# uStar.net
KiCad netlist of a schematic drawn in EAGLE
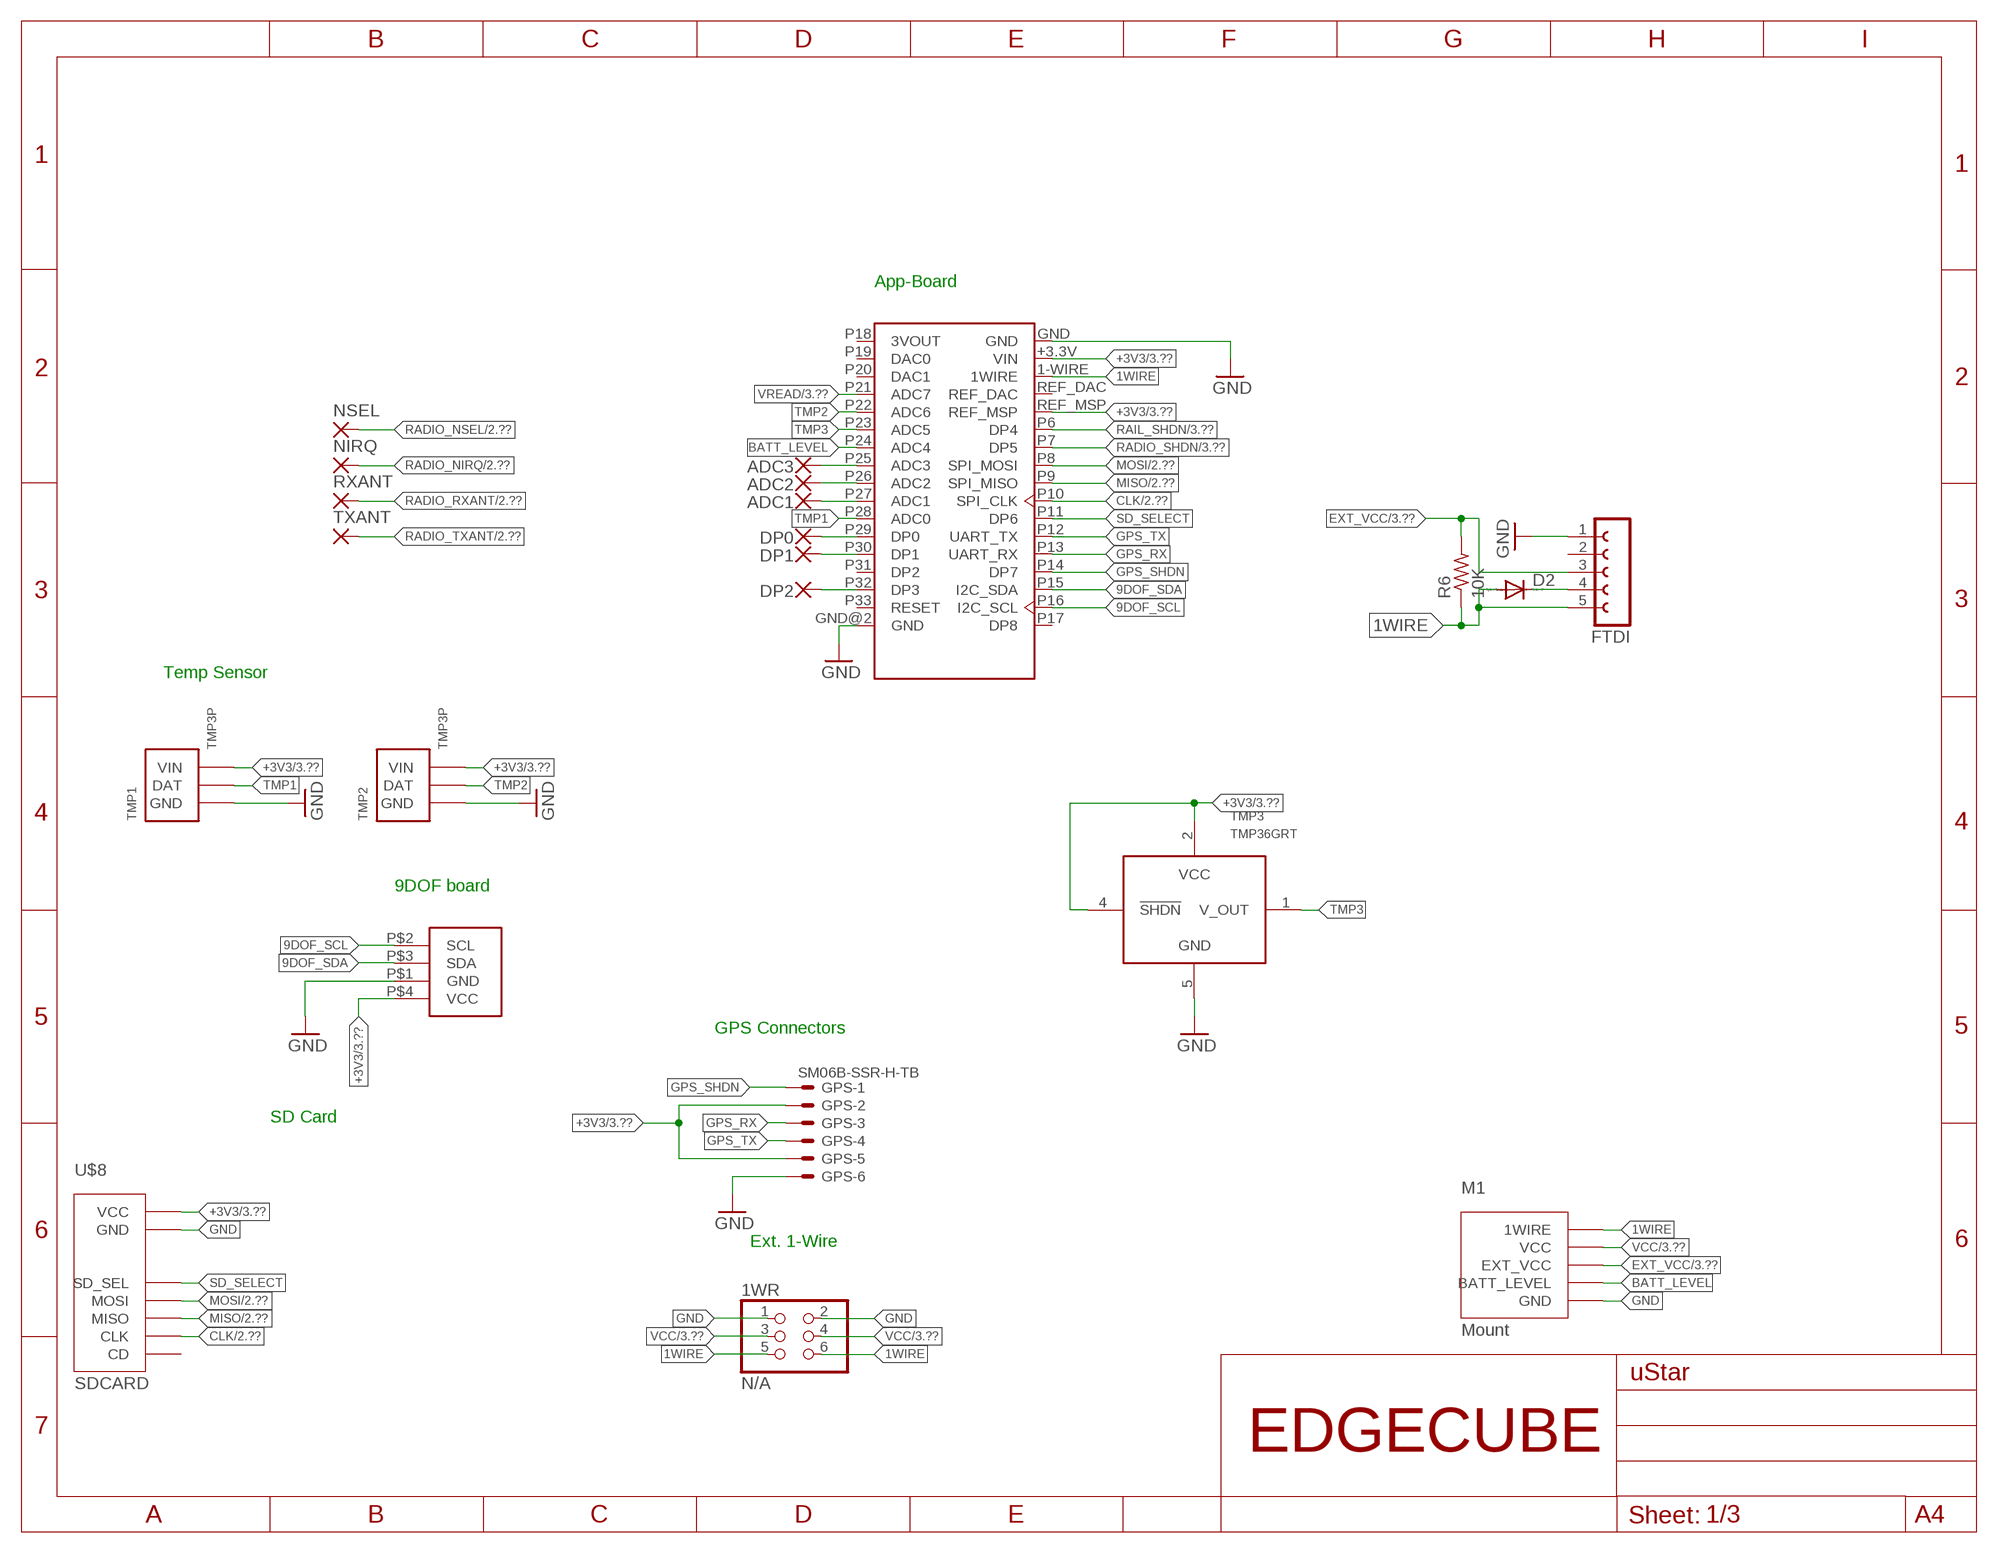
[diagram p0: schematic, sheet 1]
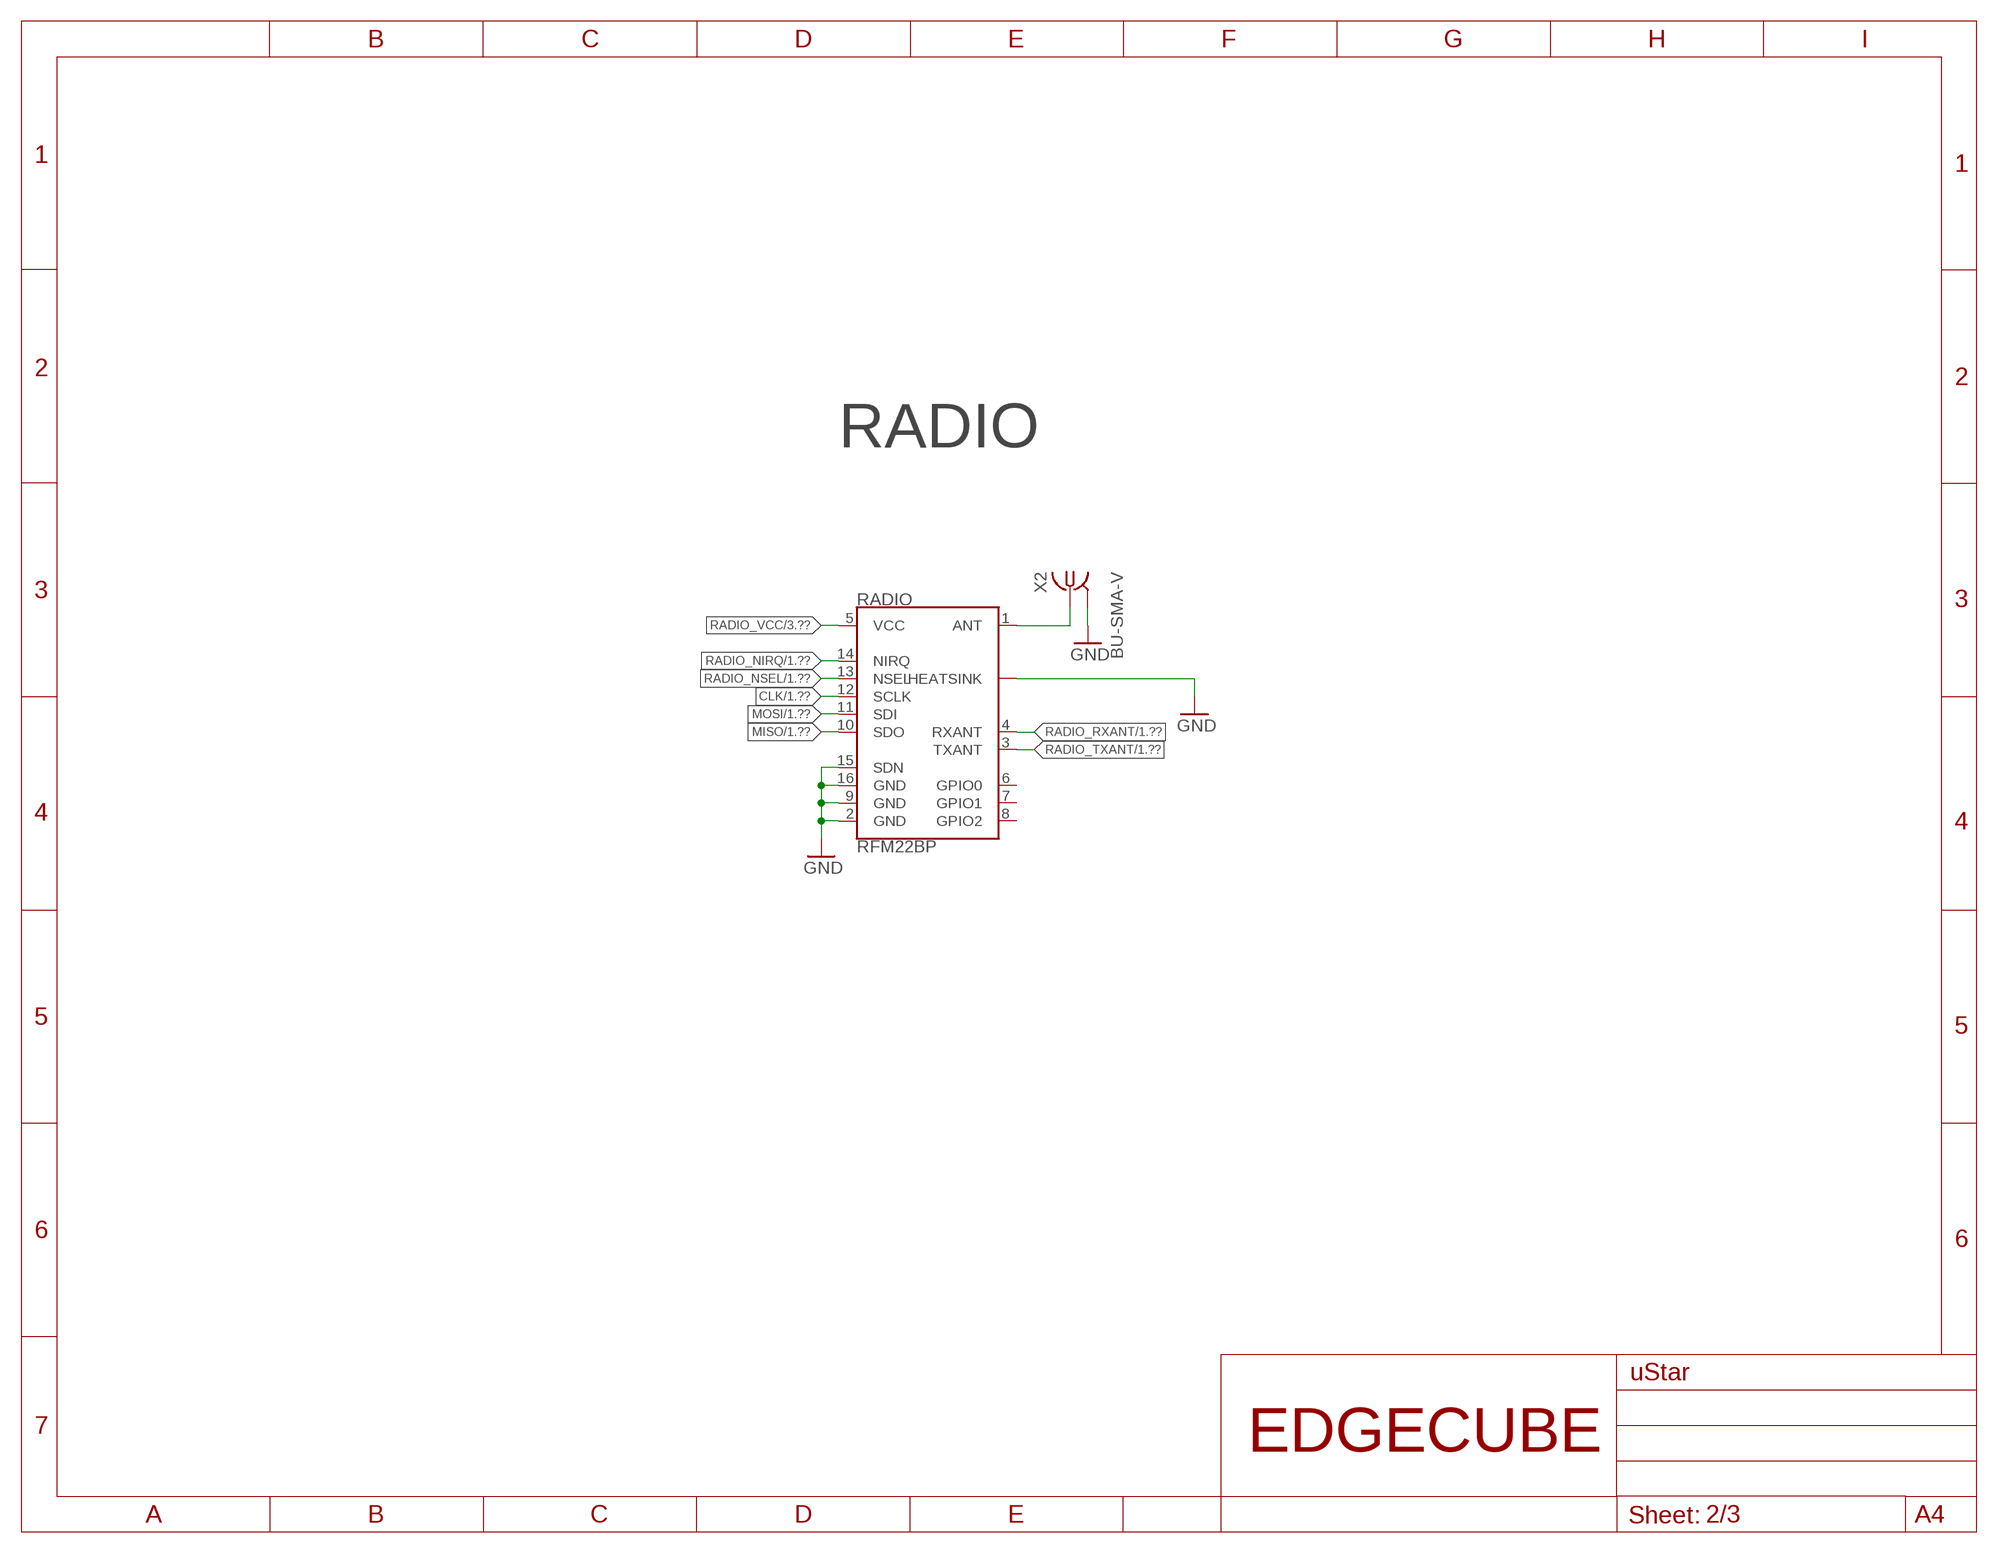
[diagram p1: schematic, sheet 2]
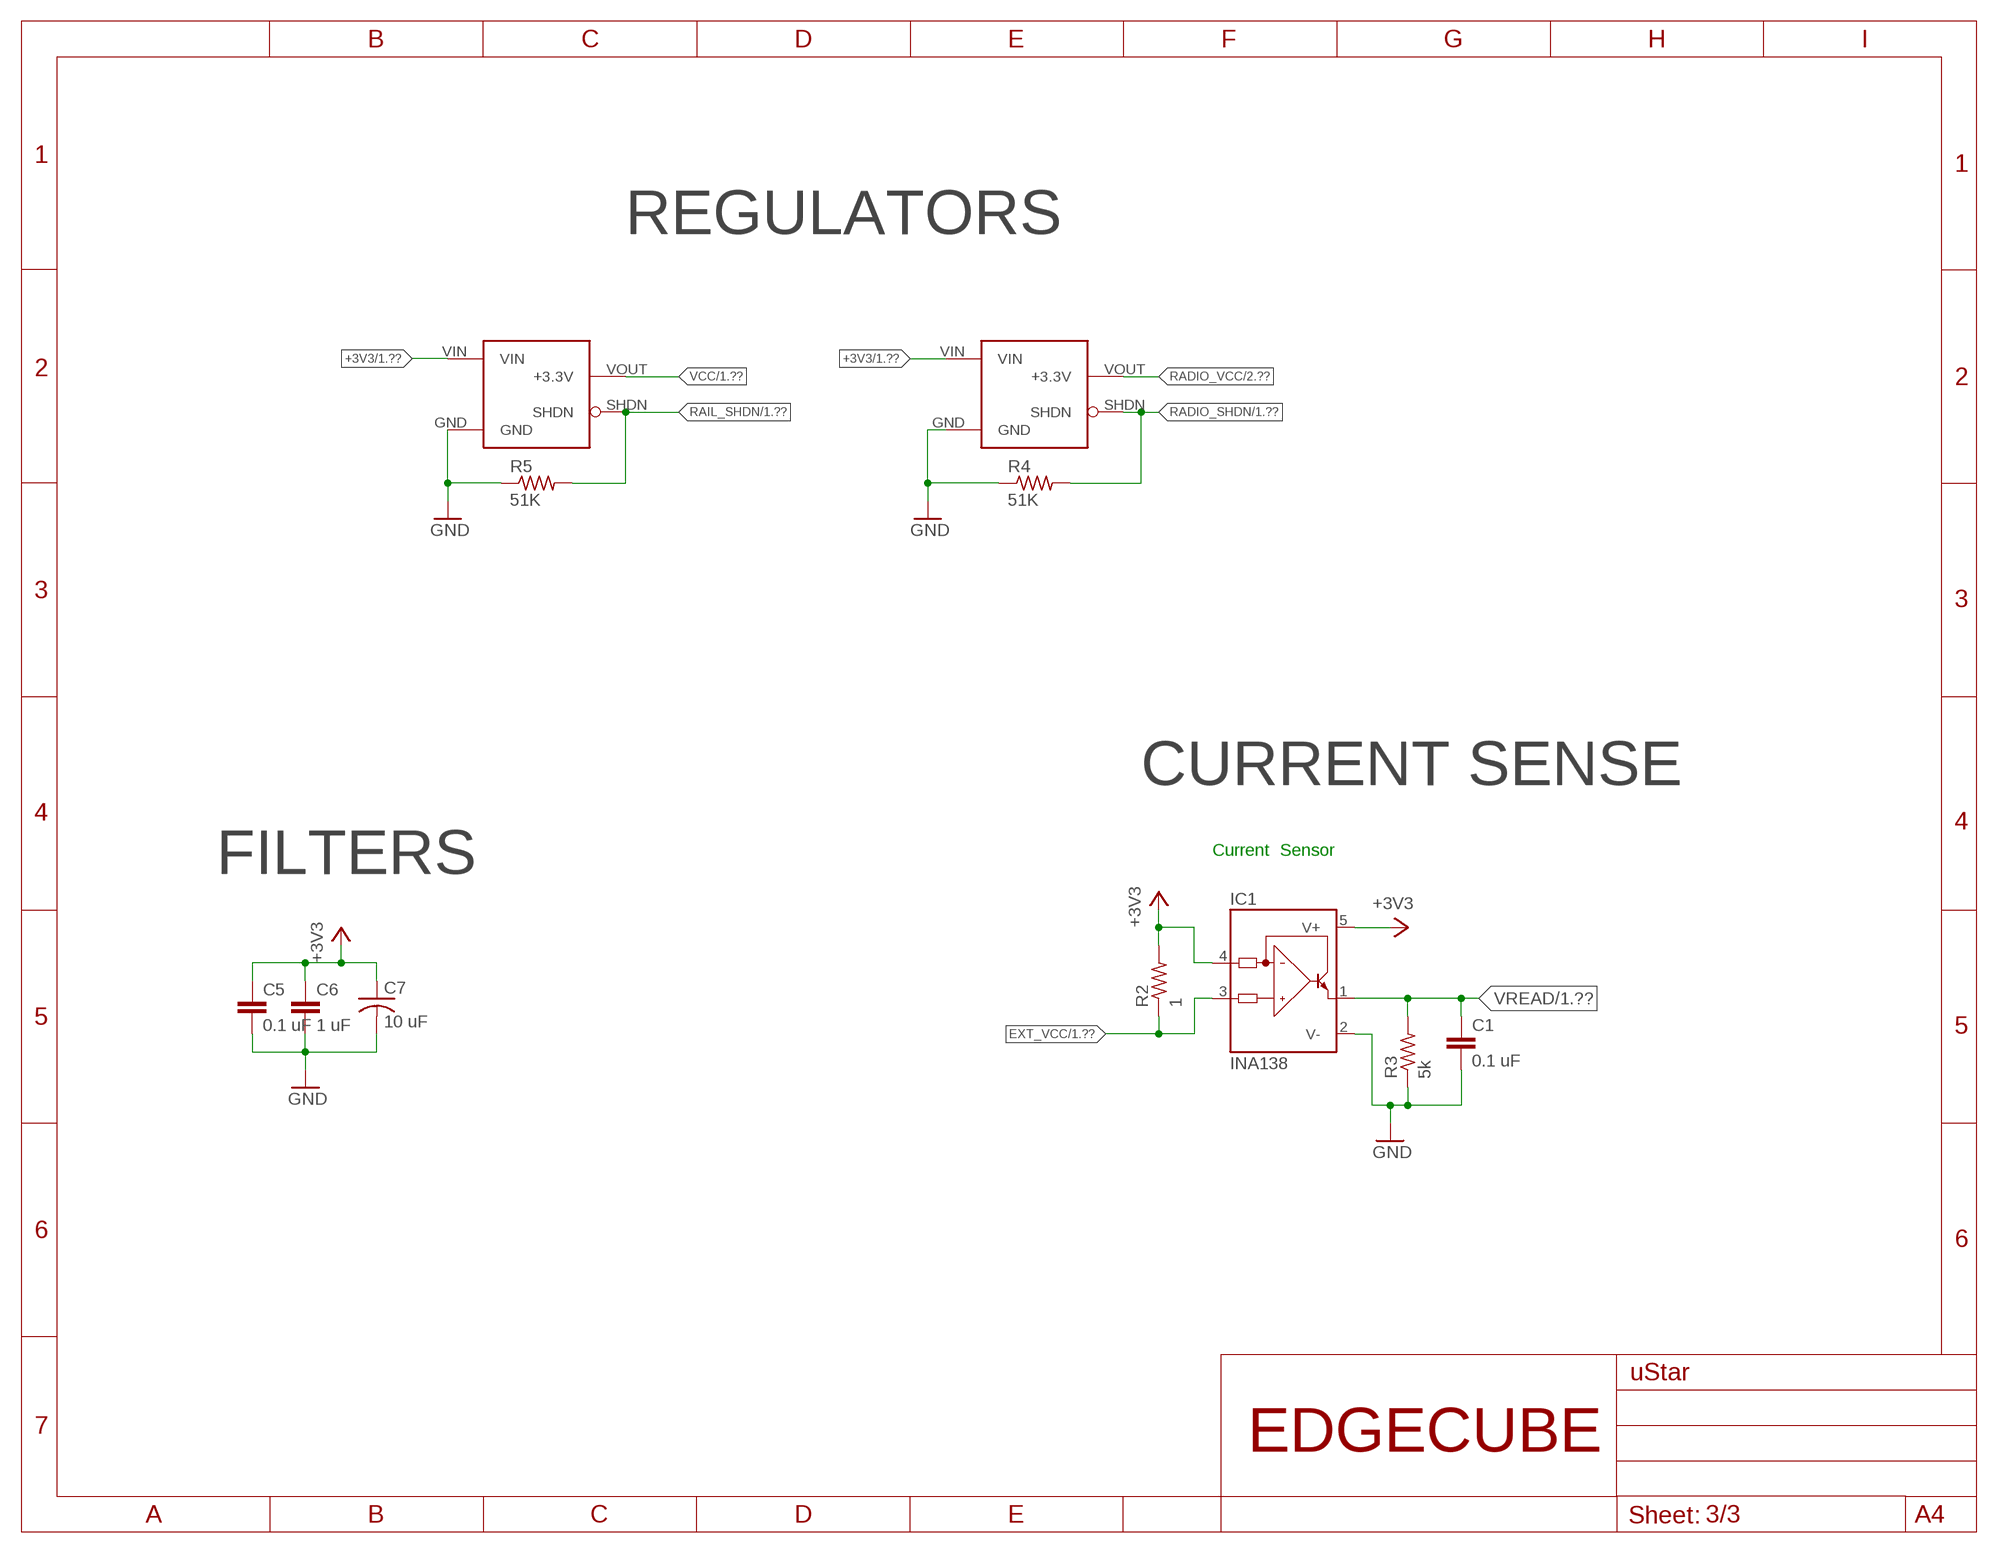
[diagram p2: schematic, sheet 3]

(export (version "E")
  (design (tool "Eeschema 10.0.6"))
  (components
    (comp (ref "C1")
      (value "0.1 uF")
      (footprint "eagle-import:C0603")
      (fields (field (name "MANUFACTURER") "AVX Corperation") (field (name "VOLTAGE") "50 V"))
      (libsource (lib "eagle-import") (part "CAP-0603-0.1UF"))
    )
    (comp (ref "C5")
      (value "0.1 uF")
      (footprint "eagle-import:C0603")
      (fields (field (name "MANUFACTURER") "AVX Corperation") (field (name "VOLTAGE") "50 V"))
      (libsource (lib "eagle-import") (part "CAP-0603-0.1UF"))
    )
    (comp (ref "C6")
      (value "1 uF")
      (footprint "eagle-import:C0603")
      (fields (field (name "MANUFACTURER") "Taiyo Yuden") (field (name "VOLTAGE") "25 V"))
      (libsource (lib "eagle-import") (part "CAP-0603-1UF"))
    )
    (comp (ref "C7")
      (value "10 uF")
      (footprint "eagle-import:C0805_POL")
      (fields (field (name "VOLTAGE") "10 V"))
      (libsource (lib "eagle-import") (part "CAP-0805-10UF-TANT"))
    )
    (comp (ref "IC1")
      (value "INA138")
      (footprint "eagle-import:SOT23-5")
      (fields (field (name "MF") "TEXAS INSTRUMENTS") (field (name "MPN") "INA138NA/250"))
      (libsource (lib "eagle-import") (part "INA138"))
    )
    (comp (ref "R2")
      (value "1")
      (footprint "eagle-import:R0603")
      (libsource (lib "eagle-import") (part "R-US_R0603"))
    )
    (comp (ref "R3")
      (value "5k")
      (footprint "eagle-import:R0603")
      (libsource (lib "eagle-import") (part "R-US_R0603"))
    )
    (comp (ref "R4")
      (value "51K")
      (footprint "eagle-import:R0603")
      (fields (field (name "MANUFACTURER") "Vishay Dale") (field (name "POWER") "0.1W"))
      (libsource (lib "eagle-import") (part "RES-0603-51K"))
    )
    (comp (ref "R5")
      (value "51K")
      (footprint "eagle-import:R0603")
      (fields (field (name "MANUFACTURER") "Vishay Dale") (field (name "POWER") "0.1W"))
      (libsource (lib "eagle-import") (part "RES-0603-51K"))
    )
    (comp (ref "U$3")
      (value "S7V8F3_VOLT_REG-3V3_1AHORZ-DOWN")
      (footprint "eagle-import:S7V_DOWN")
      (libsource (lib "eagle-import") (part "S7V8F3_VOLT_REG-3V3_1AHORZ-DOWN"))
    )
    (comp (ref "U$7")
      (value "S7V8F3_VOLT_REG-3V3_1AHORZ-DOWN")
      (footprint "eagle-import:S7V_DOWN")
      (libsource (lib "eagle-import") (part "S7V8F3_VOLT_REG-3V3_1AHORZ-DOWN"))
    )
    (comp (ref "1WR")
      (value "N/A")
      (footprint "eagle-import:2X03")
      (libsource (lib "eagle-import") (part "PINHD-2X3"))
    )
    (comp (ref "ADC1")
      (value "1,6/0,9")
      (footprint "eagle-import:1,6_0,9")
      (libsource (lib "eagle-import") (part "1,6/0,9"))
    )
    (comp (ref "ADC2")
      (value "1,6/0,9")
      (footprint "eagle-import:1,6_0,9")
      (libsource (lib "eagle-import") (part "1,6/0,9"))
    )
    (comp (ref "ADC3")
      (value "1,6/0,9")
      (footprint "eagle-import:1,6_0,9")
      (libsource (lib "eagle-import") (part "1,6/0,9"))
    )
    (comp (ref "D2")
      (value "D-B260A")
      (footprint "eagle-import:SMA-DO214AC")
      (fields (field (name "MANUFACTURER") "Diodes Incorporated") (field (name "VOLTAGE") "60V"))
      (libsource (lib "eagle-import") (part "D-B260A"))
    )
    (comp (ref "DP0")
      (value "1,6/0,9")
      (footprint "eagle-import:1,6_0,9")
      (libsource (lib "eagle-import") (part "1,6/0,9"))
    )
    (comp (ref "DP1")
      (value "1,6/0,9")
      (footprint "eagle-import:1,6_0,9")
      (libsource (lib "eagle-import") (part "1,6/0,9"))
    )
    (comp (ref "DP2")
      (value "1,6/0,9")
      (footprint "eagle-import:1,6_0,9")
      (libsource (lib "eagle-import") (part "1,6/0,9"))
    )
    (comp (ref "FTDI")
      (value "FE05-1")
      (footprint "eagle-import:FE05-1")
      (libsource (lib "eagle-import") (part "FE05-1"))
    )
    (comp (ref "GPS")
      (value "SM06B-SSR-H-TB")
      (footprint "eagle-import:SM06B-SSR-H-TB")
      (libsource (lib "eagle-import") (part "SM06B-SSR-H-TB"))
    )
    (comp (ref "M1")
      (value "Mount")
      (footprint "eagle-import:4X8MOUNT")
      (libsource (lib "eagle-import") (part "4X8MOUNT"))
    )
    (comp (ref "NIRQ")
      (value "1,6/0,9")
      (footprint "eagle-import:1,6_0,9")
      (libsource (lib "eagle-import") (part "1,6/0,9"))
    )
    (comp (ref "NSEL")
      (value "1,6/0,9")
      (footprint "eagle-import:1,6_0,9")
      (libsource (lib "eagle-import") (part "1,6/0,9"))
    )
    (comp (ref "R6")
      (value "10K")
      (footprint "eagle-import:R0603")
      (fields (field (name "MANUFACTURER") "Vishay Dale") (field (name "POWER") "0.1W"))
      (libsource (lib "eagle-import") (part "RES-0603-10K"))
    )
    (comp (ref "RXANT")
      (value "1,6/0,9")
      (footprint "eagle-import:1,6_0,9")
      (libsource (lib "eagle-import") (part "1,6/0,9"))
    )
    (comp (ref "TMP1")
      (value "TMP3P")
      (footprint "eagle-import:TMP3P")
      (libsource (lib "eagle-import") (part "TMP3P"))
    )
    (comp (ref "TMP2")
      (value "TMP3P")
      (footprint "eagle-import:TMP3P")
      (libsource (lib "eagle-import") (part "TMP3P"))
    )
    (comp (ref "TMP3")
      (value "TMP36GRT")
      (footprint "eagle-import:SOT-23-5")
      (fields (field (name "MANUFACTURER") "Analog Devices Inc.") (field (name "VOLTAGE") "2.7V-5.5V"))
      (libsource (lib "eagle-import") (part "TMP36GRT"))
    )
    (comp (ref "TXANT")
      (value "1,6/0,9")
      (footprint "eagle-import:1,6_0,9")
      (libsource (lib "eagle-import") (part "1,6/0,9"))
    )
    (comp (ref "U$1")
      (value "App-Board 1.2/1.3")
      (footprint "eagle-import:APPCORE_RECEIVER")
      (libsource (lib "eagle-import") (part "APP_CORE"))
    )
    (comp (ref "U$5")
      (value "9DOF")
      (footprint "eagle-import:9DOF")
      (libsource (lib "eagle-import") (part "9DOF"))
    )
    (comp (ref "U$8")
      (value "SDCARD")
      (footprint "eagle-import:SDCARD")
      (libsource (lib "eagle-import") (part "SDCARD"))
    )
    (comp (ref "RADIO")
      (value "RFM22BP")
      (footprint "eagle-import:RFM22BP")
      (fields (field (name "MANUFACTURER") "HOPERF Electronic"))
      (libsource (lib "eagle-import") (part "RFM22BP"))
    )
    (comp (ref "X2")
      (value "BU-SMA-V")
      (footprint "eagle-import:BU-SMA-V")
      (libsource (lib "eagle-import") (part "BU-SMA-V"))
    )
  )
  (nets
    (net (code "1") (name "+3V3") (class "Default")
      (node (ref "C5") (pin "1") (pinfunction "1_1") (pintype "passive"))
      (node (ref "C6") (pin "1") (pinfunction "1_1") (pintype "passive"))
      (node (ref "C7") (pin "2") (pinfunction "1_2") (pintype "passive"))
      (node (ref "GPS") (pin "2") (pinfunction "S_2") (pintype "passive"))
      (node (ref "GPS") (pin "5") (pinfunction "S_5") (pintype "passive"))
      (node (ref "IC1") (pin "4") (pinfunction "IN-_4") (pintype "input"))
      (node (ref "IC1") (pin "5") (pinfunction "V+_5") (pintype "power_in"))
      (node (ref "R2") (pin "2") (pinfunction "2_2") (pintype "passive"))
      (node (ref "TMP1") (pin "P$3") (pinfunction "VIN_P$3") (pintype "bidirectional"))
      (node (ref "TMP2") (pin "P$3") (pinfunction "VIN_P$3") (pintype "bidirectional"))
      (node (ref "TMP3") (pin "2") (pinfunction "VCC_2") (pintype "power_in"))
      (node (ref "TMP3") (pin "4") (pinfunction "~{SHDN}_4") (pintype "input"))
      (node (ref "U$1") (pin "+3.3V") (pinfunction "VIN_+3.3V") (pintype "power_in"))
      (node (ref "U$1") (pin "REF_MSP") (pinfunction "REF_MSP_REF_MSP") (pintype "input"))
      (node (ref "U$3") (pin "VIN") (pinfunction "VIN_VIN") (pintype "power_in"))
      (node (ref "U$5") (pin "P$4") (pinfunction "VCC_P$4") (pintype "bidirectional"))
      (node (ref "U$7") (pin "VIN") (pinfunction "VIN_VIN") (pintype "power_in"))
      (node (ref "U$8") (pin "P$3") (pinfunction "VCC_P$3") (pintype "bidirectional"))
    )
    (net (code "2") (name "1WIRE") (class "Default")
      (node (ref "1WR") (pin "5") (pinfunction "5_5") (pintype "passive"))
      (node (ref "1WR") (pin "6") (pinfunction "6_6") (pintype "passive"))
      (node (ref "D2") (pin "A") (pinfunction "A_A") (pintype "passive"))
      (node (ref "FTDI") (pin "5") (pinfunction "5_5") (pintype "passive"))
      (node (ref "M1") (pin "P$2") (pinfunction "1WIRE_P$2") (pintype "bidirectional"))
      (node (ref "M1") (pin "P$5") (pinfunction "1WIRE_P$5") (pintype "bidirectional"))
      (node (ref "R6") (pin "1") (pinfunction "1_1") (pintype "passive"))
      (node (ref "U$1") (pin "1-WIRE") (pinfunction "1WIRE_1-WIRE") (pintype "bidirectional"))
    )
    (net (code "3") (name "9DOF_SCL") (class "Default")
      (node (ref "U$1") (pin "P16") (pinfunction "I2C_SCL_P16") (pintype "bidirectional"))
      (node (ref "U$5") (pin "P$2") (pinfunction "SCL_P$2") (pintype "bidirectional"))
    )
    (net (code "4") (name "9DOF_SDA") (class "Default")
      (node (ref "U$1") (pin "P15") (pinfunction "I2C_SDA_P15") (pintype "bidirectional"))
      (node (ref "U$5") (pin "P$3") (pinfunction "SDA_P$3") (pintype "bidirectional"))
    )
    (net (code "5") (name "BATT_LEVEL") (class "Default")
      (node (ref "M1") (pin "P$6") (pinfunction "BATT_LEVEL_P$6") (pintype "bidirectional"))
      (node (ref "U$1") (pin "P24") (pinfunction "ADC4_P24") (pintype "input"))
    )
    (net (code "6") (name "CLK") (class "Default")
      (node (ref "RADIO") (pin "12") (pinfunction "SCLK_12") (pintype "input"))
      (node (ref "U$1") (pin "P10") (pinfunction "SPI_CLK_P10") (pintype "bidirectional"))
      (node (ref "U$8") (pin "P$4") (pinfunction "CLK_P$4") (pintype "bidirectional"))
    )
    (net (code "7") (name "EXT_VCC") (class "Default")
      (node (ref "FTDI") (pin "3") (pinfunction "3_3") (pintype "passive"))
      (node (ref "IC1") (pin "3") (pinfunction "IN+_3") (pintype "input"))
      (node (ref "M1") (pin "P$3") (pinfunction "EXT_VCC_P$3") (pintype "bidirectional"))
      (node (ref "R2") (pin "1") (pinfunction "1_1") (pintype "passive"))
      (node (ref "R6") (pin "2") (pinfunction "2_2") (pintype "passive"))
    )
    (net (code "8") (name "GND") (class "Default")
      (node (ref "1WR") (pin "1") (pinfunction "1_1") (pintype "passive"))
      (node (ref "1WR") (pin "2") (pinfunction "2_2") (pintype "passive"))
      (node (ref "C1") (pin "2") (pinfunction "2_2") (pintype "passive"))
      (node (ref "C5") (pin "2") (pinfunction "2_2") (pintype "passive"))
      (node (ref "C6") (pin "2") (pinfunction "2_2") (pintype "passive"))
      (node (ref "C7") (pin "1") (pinfunction "2_1") (pintype "passive"))
      (node (ref "FTDI") (pin "1") (pinfunction "1_1") (pintype "passive"))
      (node (ref "GPS") (pin "6") (pinfunction "S_6") (pintype "passive"))
      (node (ref "IC1") (pin "2") (pinfunction "V-_2") (pintype "power_in"))
      (node (ref "M1") (pin "P$1") (pinfunction "GND_P$1") (pintype "bidirectional"))
      (node (ref "M1") (pin "P$8") (pinfunction "GND_P$8") (pintype "bidirectional"))
      (node (ref "R3") (pin "1") (pinfunction "1_1") (pintype "passive"))
      (node (ref "R4") (pin "1") (pinfunction "1_1") (pintype "passive"))
      (node (ref "R5") (pin "1") (pinfunction "1_1") (pintype "passive"))
      (node (ref "RADIO") (pin "15") (pinfunction "SDN_15") (pintype "input"))
      (node (ref "RADIO") (pin "16") (pinfunction "GND_16") (pintype "power_in"))
      (node (ref "RADIO") (pin "2") (pinfunction "GND_2") (pintype "power_in"))
      (node (ref "RADIO") (pin "9") (pinfunction "GND_9") (pintype "power_in"))
      (node (ref "RADIO") (pin "P$1") (pinfunction "HEATSINK_P$1") (pintype "bidirectional"))
      (node (ref "TMP1") (pin "P$1") (pinfunction "GND_P$1") (pintype "bidirectional"))
      (node (ref "TMP2") (pin "P$1") (pinfunction "GND_P$1") (pintype "bidirectional"))
      (node (ref "TMP3") (pin "5") (pinfunction "GND_5") (pintype "power_in"))
      (node (ref "U$1") (pin "GND") (pinfunction "GND_GND") (pintype "power_in"))
      (node (ref "U$1") (pin "GND@2") (pinfunction "GND_GND@2") (pintype "power_in"))
      (node (ref "U$3") (pin "GND") (pinfunction "GND_GND") (pintype "power_in"))
      (node (ref "U$5") (pin "P$1") (pinfunction "GND_P$1") (pintype "bidirectional"))
      (node (ref "U$7") (pin "GND") (pinfunction "GND_GND") (pintype "power_in"))
      (node (ref "U$8") (pin "P$5") (pinfunction "GND_P$5") (pintype "bidirectional"))
      (node (ref "X2") (pin "2") (pinfunction "2_2") (pintype "passive"))
      (node (ref "X2") (pin "3") (pinfunction "2_3") (pintype "passive"))
      (node (ref "X2") (pin "4") (pinfunction "2_4") (pintype "passive"))
      (node (ref "X2") (pin "5") (pinfunction "2_5") (pintype "passive"))
    )
    (net (code "9") (name "GPS_RX") (class "Default")
      (node (ref "GPS") (pin "3") (pinfunction "S_3") (pintype "passive"))
      (node (ref "U$1") (pin "P13") (pinfunction "UART_RX_P13") (pintype "input"))
    )
    (net (code "10") (name "GPS_SHDN") (class "Default")
      (node (ref "GPS") (pin "1") (pinfunction "S_1") (pintype "passive"))
      (node (ref "U$1") (pin "P14") (pinfunction "DP7_P14") (pintype "bidirectional"))
    )
    (net (code "11") (name "GPS_TX") (class "Default")
      (node (ref "GPS") (pin "4") (pinfunction "S_4") (pintype "passive"))
      (node (ref "U$1") (pin "P12") (pinfunction "UART_TX_P12") (pintype "output"))
    )
    (net (code "12") (name "MISO") (class "Default")
      (node (ref "RADIO") (pin "10") (pinfunction "SDO_10") (pintype "output"))
      (node (ref "U$1") (pin "P9") (pinfunction "SPI_MISO_P9") (pintype "bidirectional"))
      (node (ref "U$8") (pin "P$6") (pinfunction "MISO_P$6") (pintype "bidirectional"))
    )
    (net (code "13") (name "MOSI") (class "Default")
      (node (ref "RADIO") (pin "11") (pinfunction "SDI_11") (pintype "input"))
      (node (ref "U$1") (pin "P8") (pinfunction "SPI_MOSI_P8") (pintype "bidirectional"))
      (node (ref "U$8") (pin "P$2") (pinfunction "MOSI_P$2") (pintype "bidirectional"))
    )
    (net (code "14") (name "Net-(ADC1-P)") (class "Default")
      (node (ref "ADC1") (pin "1") (pinfunction "P_1") (pintype "passive"))
      (node (ref "U$1") (pin "P27") (pinfunction "ADC1_P27") (pintype "input"))
    )
    (net (code "15") (name "Net-(ADC2-P)") (class "Default")
      (node (ref "ADC2") (pin "1") (pinfunction "P_1") (pintype "passive"))
      (node (ref "U$1") (pin "P26") (pinfunction "ADC2_P26") (pintype "input"))
    )
    (net (code "16") (name "Net-(ADC3-P)") (class "Default")
      (node (ref "ADC3") (pin "1") (pinfunction "P_1") (pintype "passive"))
      (node (ref "U$1") (pin "P25") (pinfunction "ADC3_P25") (pintype "input"))
    )
    (net (code "17") (name "Net-(D2-C)") (class "Default")
      (node (ref "D2") (pin "K") (pinfunction "C_K") (pintype "passive"))
      (node (ref "FTDI") (pin "4") (pinfunction "4_4") (pintype "passive"))
    )
    (net (code "18") (name "Net-(DP0-P)") (class "Default")
      (node (ref "DP0") (pin "1") (pinfunction "P_1") (pintype "passive"))
      (node (ref "U$1") (pin "P29") (pinfunction "DP0_P29") (pintype "bidirectional"))
    )
    (net (code "19") (name "Net-(DP1-P)") (class "Default")
      (node (ref "DP1") (pin "1") (pinfunction "P_1") (pintype "passive"))
      (node (ref "U$1") (pin "P30") (pinfunction "DP1_P30") (pintype "bidirectional"))
    )
    (net (code "20") (name "Net-(DP2-P)") (class "Default")
      (node (ref "DP2") (pin "1") (pinfunction "P_1") (pintype "passive"))
      (node (ref "U$1") (pin "P32") (pinfunction "DP3_P32") (pintype "bidirectional"))
    )
    (net (code "21") (name "Net-(RADIO-ANT)") (class "Default")
      (node (ref "RADIO") (pin "1") (pinfunction "ANT_1") (pintype "bidirectional"))
      (node (ref "X2") (pin "1") (pinfunction "1_1") (pintype "passive"))
    )
    (net (code "22") (name "RADIO_NIRQ") (class "Default")
      (node (ref "NIRQ") (pin "1") (pinfunction "P_1") (pintype "passive"))
      (node (ref "RADIO") (pin "14") (pinfunction "NIRQ_14") (pintype "output"))
    )
    (net (code "23") (name "RADIO_NSEL") (class "Default")
      (node (ref "NSEL") (pin "1") (pinfunction "P_1") (pintype "passive"))
      (node (ref "RADIO") (pin "13") (pinfunction "NSEL_13") (pintype "input"))
    )
    (net (code "24") (name "RADIO_RXANT") (class "Default")
      (node (ref "RADIO") (pin "4") (pinfunction "RXANT_4") (pintype "input"))
      (node (ref "RXANT") (pin "1") (pinfunction "P_1") (pintype "passive"))
    )
    (net (code "25") (name "RADIO_SHDN") (class "Default")
      (node (ref "R4") (pin "2") (pinfunction "2_2") (pintype "passive"))
      (node (ref "U$1") (pin "P7") (pinfunction "DP5_P7") (pintype "bidirectional"))
      (node (ref "U$7") (pin "SHDN") (pinfunction "SHDN_SHDN") (pintype "input"))
    )
    (net (code "26") (name "RADIO_TXANT") (class "Default")
      (node (ref "RADIO") (pin "3") (pinfunction "TXANT_3") (pintype "input"))
      (node (ref "TXANT") (pin "1") (pinfunction "P_1") (pintype "passive"))
    )
    (net (code "27") (name "RADIO_VCC") (class "Default")
      (node (ref "RADIO") (pin "5") (pinfunction "VCC_5") (pintype "bidirectional"))
      (node (ref "U$7") (pin "VOUT") (pinfunction "+3.3V_VOUT") (pintype "output"))
    )
    (net (code "28") (name "RAIL_SHDN") (class "Default")
      (node (ref "R5") (pin "2") (pinfunction "2_2") (pintype "passive"))
      (node (ref "U$1") (pin "P6") (pinfunction "DP4_P6") (pintype "bidirectional"))
      (node (ref "U$3") (pin "SHDN") (pinfunction "SHDN_SHDN") (pintype "input"))
    )
    (net (code "29") (name "SD_SELECT") (class "Default")
      (node (ref "U$1") (pin "P11") (pinfunction "DP6_P11") (pintype "bidirectional"))
      (node (ref "U$8") (pin "P$1") (pinfunction "SD_SEL_P$1") (pintype "bidirectional"))
    )
    (net (code "30") (name "TMP1") (class "Default")
      (node (ref "TMP1") (pin "P$2") (pinfunction "DAT_P$2") (pintype "bidirectional"))
      (node (ref "U$1") (pin "P28") (pinfunction "ADC0_P28") (pintype "input"))
    )
    (net (code "31") (name "TMP2") (class "Default")
      (node (ref "TMP2") (pin "P$2") (pinfunction "DAT_P$2") (pintype "bidirectional"))
      (node (ref "U$1") (pin "P22") (pinfunction "ADC6_P22") (pintype "input"))
    )
    (net (code "32") (name "TMP3") (class "Default")
      (node (ref "TMP3") (pin "1") (pinfunction "V_OUT_1") (pintype "output"))
      (node (ref "U$1") (pin "P23") (pinfunction "ADC5_P23") (pintype "input"))
    )
    (net (code "33") (name "VCC") (class "Default")
      (node (ref "1WR") (pin "3") (pinfunction "3_3") (pintype "passive"))
      (node (ref "1WR") (pin "4") (pinfunction "4_4") (pintype "passive"))
      (node (ref "M1") (pin "P$4") (pinfunction "VCC_P$4") (pintype "bidirectional"))
      (node (ref "M1") (pin "P$7") (pinfunction "VCC_P$7") (pintype "bidirectional"))
      (node (ref "U$3") (pin "VOUT") (pinfunction "+3.3V_VOUT") (pintype "output"))
    )
    (net (code "34") (name "VREAD") (class "Default")
      (node (ref "C1") (pin "1") (pinfunction "1_1") (pintype "passive"))
      (node (ref "IC1") (pin "1") (pinfunction "OUT_1") (pintype "output"))
      (node (ref "R3") (pin "2") (pinfunction "2_2") (pintype "passive"))
      (node (ref "U$1") (pin "P21") (pinfunction "ADC7_P21") (pintype "input"))
    )
    (net (code "35") (name "unconnected-(FTDI-Pad2)") (class "Default")
      (node (ref "FTDI") (pin "2") (pinfunction "2_2") (pintype "passive"))
    )
    (net (code "36") (name "unconnected-(RADIO-GPIO0-Pad6)") (class "Default")
      (node (ref "RADIO") (pin "6") (pinfunction "GPIO0_6") (pintype "bidirectional"))
    )
    (net (code "37") (name "unconnected-(RADIO-GPIO1-Pad7)") (class "Default")
      (node (ref "RADIO") (pin "7") (pinfunction "GPIO1_7") (pintype "bidirectional"))
    )
    (net (code "38") (name "unconnected-(RADIO-GPIO2-Pad8)") (class "Default")
      (node (ref "RADIO") (pin "8") (pinfunction "GPIO2_8") (pintype "bidirectional"))
    )
    (net (code "39") (name "unconnected-(U$1-3VOUT-PadP18)") (class "Default")
      (node (ref "U$1") (pin "P18") (pinfunction "3VOUT_P18") (pintype "output"))
    )
    (net (code "40") (name "unconnected-(U$1-DAC0-PadP19)") (class "Default")
      (node (ref "U$1") (pin "P19") (pinfunction "DAC0_P19") (pintype "bidirectional"))
    )
    (net (code "41") (name "unconnected-(U$1-DAC1-PadP20)") (class "Default")
      (node (ref "U$1") (pin "P20") (pinfunction "DAC1_P20") (pintype "bidirectional"))
    )
    (net (code "42") (name "unconnected-(U$1-DP2-PadP31)") (class "Default")
      (node (ref "U$1") (pin "P31") (pinfunction "DP2_P31") (pintype "bidirectional"))
    )
    (net (code "43") (name "unconnected-(U$1-DP8-PadP17)") (class "Default")
      (node (ref "U$1") (pin "P17") (pinfunction "DP8_P17") (pintype "bidirectional"))
    )
    (net (code "44") (name "unconnected-(U$1-PadREF_DAC)") (class "Default")
      (node (ref "U$1") (pin "REF_DAC") (pinfunction "REF_DAC_REF_DAC") (pintype "input"))
    )
    (net (code "45") (name "unconnected-(U$1-RESET-PadP33)") (class "Default")
      (node (ref "U$1") (pin "P33") (pinfunction "RESET_P33") (pintype "bidirectional"))
    )
    (net (code "46") (name "unconnected-(U$8-CD-PadP$7)") (class "Default")
      (node (ref "U$8") (pin "P$7") (pinfunction "CD_P$7") (pintype "bidirectional"))
    )
  )
)
